# EIT_Teensy_Mux.net
KiCad netlist of a schematic drawn in Altium Designer
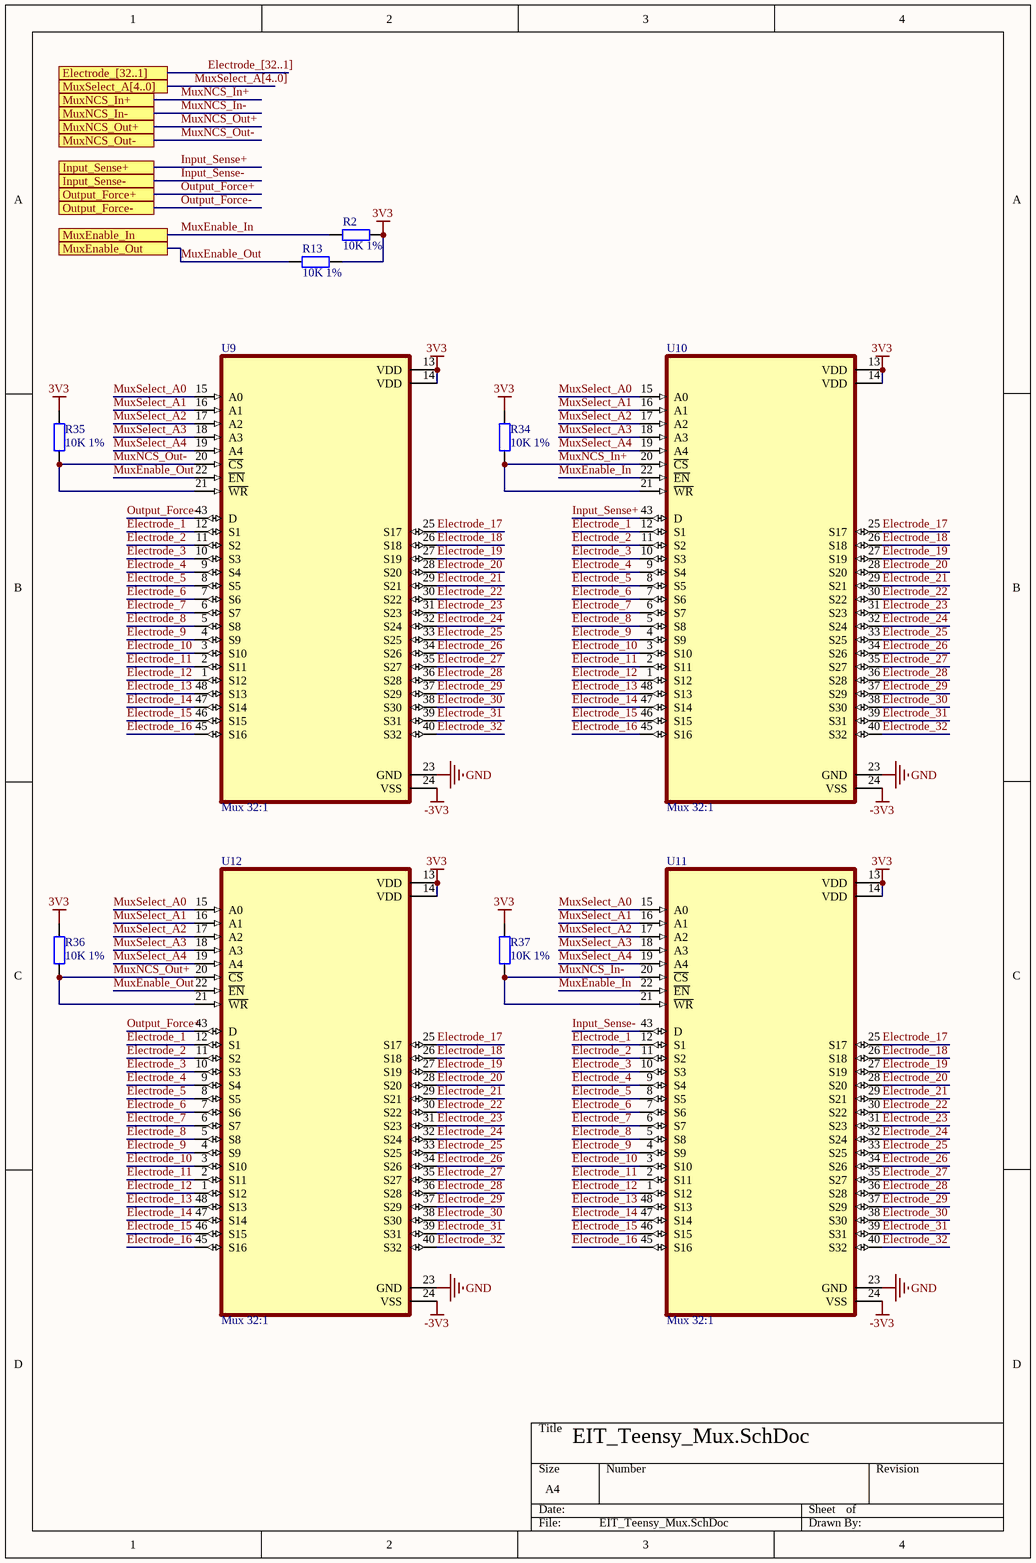
[diagram p0: EIT_Teensy_Mux.SchDoc]

(export (version "E")
  (design (tool "Eeschema 10.0.6"))
  (components
    (comp (ref "R2")
      (value "10K 1%")
      (footprint "0603 RES")
      (description "Res General Purpose Thick Film 0603 10K Ohm 1% 1/10W ±100ppm/°C Molded SMD Paper T/R")
      (fields
        (field (name "MANUFACTURER") "Yageo")
        (field (name "MANUFACTURER PART NUMBER") "RC0603FR-0710KL")
      )
      (libsource (lib "EitLib") (part "Res 0603 10K 1%"))
    )
    (comp (ref "R13")
      (value "10K 1%")
      (footprint "0603 RES")
      (description "Res General Purpose Thick Film 0603 10K Ohm 1% 1/10W ±100ppm/°C Molded SMD Paper T/R")
      (fields
        (field (name "MANUFACTURER") "Yageo")
        (field (name "MANUFACTURER PART NUMBER") "RC0603FR-0710KL")
      )
      (libsource (lib "EitLib") (part "Res 0603 10K 1%"))
    )
    (comp (ref "R34")
      (value "10K 1%")
      (footprint "0603 RES")
      (description "Res General Purpose Thick Film 0603 10K Ohm 1% 1/10W ±100ppm/°C Molded SMD Paper T/R")
      (fields
        (field (name "MANUFACTURER") "Yageo")
        (field (name "MANUFACTURER PART NUMBER") "RC0603FR-0710KL")
      )
      (libsource (lib "") (part "Res 0603 10K 1%_1"))
    )
    (comp (ref "R35")
      (value "10K 1%")
      (footprint "0603 RES")
      (description "Res General Purpose Thick Film 0603 10K Ohm 1% 1/10W ±100ppm/°C Molded SMD Paper T/R")
      (fields
        (field (name "MANUFACTURER") "Yageo")
        (field (name "MANUFACTURER PART NUMBER") "RC0603FR-0710KL")
      )
      (libsource (lib "") (part "Res 0603 10K 1%_1"))
    )
    (comp (ref "R36")
      (value "10K 1%")
      (footprint "0603 RES")
      (description "Res General Purpose Thick Film 0603 10K Ohm 1% 1/10W ±100ppm/°C Molded SMD Paper T/R")
      (fields
        (field (name "MANUFACTURER") "Yageo")
        (field (name "MANUFACTURER PART NUMBER") "RC0603FR-0710KL")
      )
      (libsource (lib "") (part "Res 0603 10K 1%_1"))
    )
    (comp (ref "R37")
      (value "10K 1%")
      (footprint "0603 RES")
      (description "Res General Purpose Thick Film 0603 10K Ohm 1% 1/10W ±100ppm/°C Molded SMD Paper T/R")
      (fields
        (field (name "MANUFACTURER") "Yageo")
        (field (name "MANUFACTURER PART NUMBER") "RC0603FR-0710KL")
      )
      (libsource (lib "") (part "Res 0603 10K 1%_1"))
    )
    (comp (ref "U9")
      (value "Mux 32:1")
      (footprint "SnapEDApcb:QFP50P900X900X120-49N")
      (description "Analog Multiplexer Single 32:1 48-Pin TQFP T/R")
      (fields
        (field (name "MANUFACTURER") "Analog Devices")
        (field (name "MANUFACTURER PART NUMBER") "ADG732BSUZ-REEL")
      )
      (libsource (lib "EitLib") (part "Mux ADG732BSUZ"))
    )
    (comp (ref "U10")
      (value "Mux 32:1")
      (footprint "SnapEDApcb:QFP50P900X900X120-49N")
      (description "Analog Multiplexer Single 32:1 48-Pin TQFP T/R")
      (fields
        (field (name "MANUFACTURER") "Analog Devices")
        (field (name "MANUFACTURER PART NUMBER") "ADG732BSUZ-REEL")
      )
      (libsource (lib "EitLib") (part "Mux ADG732BSUZ"))
    )
    (comp (ref "U11")
      (value "Mux 32:1")
      (footprint "SnapEDApcb:QFP50P900X900X120-49N")
      (description "Analog Multiplexer Single 32:1 48-Pin TQFP T/R")
      (fields
        (field (name "MANUFACTURER") "Analog Devices")
        (field (name "MANUFACTURER PART NUMBER") "ADG732BSUZ-REEL")
      )
      (libsource (lib "EitLib") (part "Mux ADG732BSUZ"))
    )
    (comp (ref "U12")
      (value "Mux 32:1")
      (footprint "SnapEDApcb:QFP50P900X900X120-49N")
      (description "Analog Multiplexer Single 32:1 48-Pin TQFP T/R")
      (fields
        (field (name "MANUFACTURER") "Analog Devices")
        (field (name "MANUFACTURER PART NUMBER") "ADG732BSUZ-REEL")
      )
      (libsource (lib "EitLib") (part "Mux ADG732BSUZ"))
    )
  )
  (nets
    (net (code "1") (name "-3V3") (class "Default")
      (node (ref "U10") (pin "24") (pinfunction "VSS_24") (pintype "power_in"))
      (node (ref "U11") (pin "24") (pinfunction "VSS_24") (pintype "power_in"))
      (node (ref "U12") (pin "24") (pinfunction "VSS_24") (pintype "power_in"))
      (node (ref "U9") (pin "24") (pinfunction "VSS_24") (pintype "power_in"))
    )
    (net (code "2") (name "/Electrode_1") (class "Default")
      (node (ref "U10") (pin "12") (pinfunction "S1_12") (pintype "bidirectional"))
      (node (ref "U11") (pin "12") (pinfunction "S1_12") (pintype "bidirectional"))
      (node (ref "U12") (pin "12") (pinfunction "S1_12") (pintype "bidirectional"))
      (node (ref "U9") (pin "12") (pinfunction "S1_12") (pintype "bidirectional"))
    )
    (net (code "3") (name "/Electrode_2") (class "Default")
      (node (ref "U10") (pin "11") (pinfunction "S2_11") (pintype "bidirectional"))
      (node (ref "U11") (pin "11") (pinfunction "S2_11") (pintype "bidirectional"))
      (node (ref "U12") (pin "11") (pinfunction "S2_11") (pintype "bidirectional"))
      (node (ref "U9") (pin "11") (pinfunction "S2_11") (pintype "bidirectional"))
    )
    (net (code "4") (name "/Electrode_3") (class "Default")
      (node (ref "U10") (pin "10") (pinfunction "S3_10") (pintype "bidirectional"))
      (node (ref "U11") (pin "10") (pinfunction "S3_10") (pintype "bidirectional"))
      (node (ref "U12") (pin "10") (pinfunction "S3_10") (pintype "bidirectional"))
      (node (ref "U9") (pin "10") (pinfunction "S3_10") (pintype "bidirectional"))
    )
    (net (code "5") (name "/Electrode_4") (class "Default")
      (node (ref "U10") (pin "9") (pinfunction "S4_9") (pintype "bidirectional"))
      (node (ref "U11") (pin "9") (pinfunction "S4_9") (pintype "bidirectional"))
      (node (ref "U12") (pin "9") (pinfunction "S4_9") (pintype "bidirectional"))
      (node (ref "U9") (pin "9") (pinfunction "S4_9") (pintype "bidirectional"))
    )
    (net (code "6") (name "/Electrode_5") (class "Default")
      (node (ref "U10") (pin "8") (pinfunction "S5_8") (pintype "bidirectional"))
      (node (ref "U11") (pin "8") (pinfunction "S5_8") (pintype "bidirectional"))
      (node (ref "U12") (pin "8") (pinfunction "S5_8") (pintype "bidirectional"))
      (node (ref "U9") (pin "8") (pinfunction "S5_8") (pintype "bidirectional"))
    )
    (net (code "7") (name "/Electrode_6") (class "Default")
      (node (ref "U10") (pin "7") (pinfunction "S6_7") (pintype "bidirectional"))
      (node (ref "U11") (pin "7") (pinfunction "S6_7") (pintype "bidirectional"))
      (node (ref "U12") (pin "7") (pinfunction "S6_7") (pintype "bidirectional"))
      (node (ref "U9") (pin "7") (pinfunction "S6_7") (pintype "bidirectional"))
    )
    (net (code "8") (name "/Electrode_7") (class "Default")
      (node (ref "U10") (pin "6") (pinfunction "S7_6") (pintype "bidirectional"))
      (node (ref "U11") (pin "6") (pinfunction "S7_6") (pintype "bidirectional"))
      (node (ref "U12") (pin "6") (pinfunction "S7_6") (pintype "bidirectional"))
      (node (ref "U9") (pin "6") (pinfunction "S7_6") (pintype "bidirectional"))
    )
    (net (code "9") (name "/Electrode_8") (class "Default")
      (node (ref "U10") (pin "5") (pinfunction "S8_5") (pintype "bidirectional"))
      (node (ref "U11") (pin "5") (pinfunction "S8_5") (pintype "bidirectional"))
      (node (ref "U12") (pin "5") (pinfunction "S8_5") (pintype "bidirectional"))
      (node (ref "U9") (pin "5") (pinfunction "S8_5") (pintype "bidirectional"))
    )
    (net (code "10") (name "/Electrode_9") (class "Default")
      (node (ref "U10") (pin "4") (pinfunction "S9_4") (pintype "bidirectional"))
      (node (ref "U11") (pin "4") (pinfunction "S9_4") (pintype "bidirectional"))
      (node (ref "U12") (pin "4") (pinfunction "S9_4") (pintype "bidirectional"))
      (node (ref "U9") (pin "4") (pinfunction "S9_4") (pintype "bidirectional"))
    )
    (net (code "11") (name "/Electrode_10") (class "Default")
      (node (ref "U10") (pin "3") (pinfunction "S10_3") (pintype "bidirectional"))
      (node (ref "U11") (pin "3") (pinfunction "S10_3") (pintype "bidirectional"))
      (node (ref "U12") (pin "3") (pinfunction "S10_3") (pintype "bidirectional"))
      (node (ref "U9") (pin "3") (pinfunction "S10_3") (pintype "bidirectional"))
    )
    (net (code "12") (name "/Electrode_11") (class "Default")
      (node (ref "U10") (pin "2") (pinfunction "S11_2") (pintype "bidirectional"))
      (node (ref "U11") (pin "2") (pinfunction "S11_2") (pintype "bidirectional"))
      (node (ref "U12") (pin "2") (pinfunction "S11_2") (pintype "bidirectional"))
      (node (ref "U9") (pin "2") (pinfunction "S11_2") (pintype "bidirectional"))
    )
    (net (code "13") (name "/Electrode_12") (class "Default")
      (node (ref "U10") (pin "1") (pinfunction "S12_1") (pintype "bidirectional"))
      (node (ref "U11") (pin "1") (pinfunction "S12_1") (pintype "bidirectional"))
      (node (ref "U12") (pin "1") (pinfunction "S12_1") (pintype "bidirectional"))
      (node (ref "U9") (pin "1") (pinfunction "S12_1") (pintype "bidirectional"))
    )
    (net (code "14") (name "/Electrode_13") (class "Default")
      (node (ref "U10") (pin "48") (pinfunction "S13_48") (pintype "bidirectional"))
      (node (ref "U11") (pin "48") (pinfunction "S13_48") (pintype "bidirectional"))
      (node (ref "U12") (pin "48") (pinfunction "S13_48") (pintype "bidirectional"))
      (node (ref "U9") (pin "48") (pinfunction "S13_48") (pintype "bidirectional"))
    )
    (net (code "15") (name "/Electrode_14") (class "Default")
      (node (ref "U10") (pin "47") (pinfunction "S14_47") (pintype "bidirectional"))
      (node (ref "U11") (pin "47") (pinfunction "S14_47") (pintype "bidirectional"))
      (node (ref "U12") (pin "47") (pinfunction "S14_47") (pintype "bidirectional"))
      (node (ref "U9") (pin "47") (pinfunction "S14_47") (pintype "bidirectional"))
    )
    (net (code "16") (name "/Electrode_15") (class "Default")
      (node (ref "U10") (pin "46") (pinfunction "S15_46") (pintype "bidirectional"))
      (node (ref "U11") (pin "46") (pinfunction "S15_46") (pintype "bidirectional"))
      (node (ref "U12") (pin "46") (pinfunction "S15_46") (pintype "bidirectional"))
      (node (ref "U9") (pin "46") (pinfunction "S15_46") (pintype "bidirectional"))
    )
    (net (code "17") (name "/Electrode_16") (class "Default")
      (node (ref "U10") (pin "45") (pinfunction "S16_45") (pintype "bidirectional"))
      (node (ref "U11") (pin "45") (pinfunction "S16_45") (pintype "bidirectional"))
      (node (ref "U12") (pin "45") (pinfunction "S16_45") (pintype "bidirectional"))
      (node (ref "U9") (pin "45") (pinfunction "S16_45") (pintype "bidirectional"))
    )
    (net (code "18") (name "/Electrode_17") (class "Default")
      (node (ref "U10") (pin "25") (pinfunction "S17_25") (pintype "bidirectional"))
      (node (ref "U11") (pin "25") (pinfunction "S17_25") (pintype "bidirectional"))
      (node (ref "U12") (pin "25") (pinfunction "S17_25") (pintype "bidirectional"))
      (node (ref "U9") (pin "25") (pinfunction "S17_25") (pintype "bidirectional"))
    )
    (net (code "19") (name "/Electrode_18") (class "Default")
      (node (ref "U10") (pin "26") (pinfunction "S18_26") (pintype "bidirectional"))
      (node (ref "U11") (pin "26") (pinfunction "S18_26") (pintype "bidirectional"))
      (node (ref "U12") (pin "26") (pinfunction "S18_26") (pintype "bidirectional"))
      (node (ref "U9") (pin "26") (pinfunction "S18_26") (pintype "bidirectional"))
    )
    (net (code "20") (name "/Electrode_19") (class "Default")
      (node (ref "U10") (pin "27") (pinfunction "S19_27") (pintype "bidirectional"))
      (node (ref "U11") (pin "27") (pinfunction "S19_27") (pintype "bidirectional"))
      (node (ref "U12") (pin "27") (pinfunction "S19_27") (pintype "bidirectional"))
      (node (ref "U9") (pin "27") (pinfunction "S19_27") (pintype "bidirectional"))
    )
    (net (code "21") (name "/Electrode_20") (class "Default")
      (node (ref "U10") (pin "28") (pinfunction "S20_28") (pintype "bidirectional"))
      (node (ref "U11") (pin "28") (pinfunction "S20_28") (pintype "bidirectional"))
      (node (ref "U12") (pin "28") (pinfunction "S20_28") (pintype "bidirectional"))
      (node (ref "U9") (pin "28") (pinfunction "S20_28") (pintype "bidirectional"))
    )
    (net (code "22") (name "/Electrode_21") (class "Default")
      (node (ref "U10") (pin "29") (pinfunction "S21_29") (pintype "bidirectional"))
      (node (ref "U11") (pin "29") (pinfunction "S21_29") (pintype "bidirectional"))
      (node (ref "U12") (pin "29") (pinfunction "S21_29") (pintype "bidirectional"))
      (node (ref "U9") (pin "29") (pinfunction "S21_29") (pintype "bidirectional"))
    )
    (net (code "23") (name "/Electrode_22") (class "Default")
      (node (ref "U10") (pin "30") (pinfunction "S22_30") (pintype "bidirectional"))
      (node (ref "U11") (pin "30") (pinfunction "S22_30") (pintype "bidirectional"))
      (node (ref "U12") (pin "30") (pinfunction "S22_30") (pintype "bidirectional"))
      (node (ref "U9") (pin "30") (pinfunction "S22_30") (pintype "bidirectional"))
    )
    (net (code "24") (name "/Electrode_23") (class "Default")
      (node (ref "U10") (pin "31") (pinfunction "S23_31") (pintype "bidirectional"))
      (node (ref "U11") (pin "31") (pinfunction "S23_31") (pintype "bidirectional"))
      (node (ref "U12") (pin "31") (pinfunction "S23_31") (pintype "bidirectional"))
      (node (ref "U9") (pin "31") (pinfunction "S23_31") (pintype "bidirectional"))
    )
    (net (code "25") (name "/Electrode_24") (class "Default")
      (node (ref "U10") (pin "32") (pinfunction "S24_32") (pintype "bidirectional"))
      (node (ref "U11") (pin "32") (pinfunction "S24_32") (pintype "bidirectional"))
      (node (ref "U12") (pin "32") (pinfunction "S24_32") (pintype "bidirectional"))
      (node (ref "U9") (pin "32") (pinfunction "S24_32") (pintype "bidirectional"))
    )
    (net (code "26") (name "/Electrode_25") (class "Default")
      (node (ref "U10") (pin "33") (pinfunction "S25_33") (pintype "bidirectional"))
      (node (ref "U11") (pin "33") (pinfunction "S25_33") (pintype "bidirectional"))
      (node (ref "U12") (pin "33") (pinfunction "S25_33") (pintype "bidirectional"))
      (node (ref "U9") (pin "33") (pinfunction "S25_33") (pintype "bidirectional"))
    )
    (net (code "27") (name "/Electrode_26") (class "Default")
      (node (ref "U10") (pin "34") (pinfunction "S26_34") (pintype "bidirectional"))
      (node (ref "U11") (pin "34") (pinfunction "S26_34") (pintype "bidirectional"))
      (node (ref "U12") (pin "34") (pinfunction "S26_34") (pintype "bidirectional"))
      (node (ref "U9") (pin "34") (pinfunction "S26_34") (pintype "bidirectional"))
    )
    (net (code "28") (name "/Electrode_27") (class "Default")
      (node (ref "U10") (pin "35") (pinfunction "S27_35") (pintype "bidirectional"))
      (node (ref "U11") (pin "35") (pinfunction "S27_35") (pintype "bidirectional"))
      (node (ref "U12") (pin "35") (pinfunction "S27_35") (pintype "bidirectional"))
      (node (ref "U9") (pin "35") (pinfunction "S27_35") (pintype "bidirectional"))
    )
    (net (code "29") (name "/Electrode_28") (class "Default")
      (node (ref "U10") (pin "36") (pinfunction "S28_36") (pintype "bidirectional"))
      (node (ref "U11") (pin "36") (pinfunction "S28_36") (pintype "bidirectional"))
      (node (ref "U12") (pin "36") (pinfunction "S28_36") (pintype "bidirectional"))
      (node (ref "U9") (pin "36") (pinfunction "S28_36") (pintype "bidirectional"))
    )
    (net (code "30") (name "/Electrode_29") (class "Default")
      (node (ref "U10") (pin "37") (pinfunction "S29_37") (pintype "bidirectional"))
      (node (ref "U11") (pin "37") (pinfunction "S29_37") (pintype "bidirectional"))
      (node (ref "U12") (pin "37") (pinfunction "S29_37") (pintype "bidirectional"))
      (node (ref "U9") (pin "37") (pinfunction "S29_37") (pintype "bidirectional"))
    )
    (net (code "31") (name "/Electrode_30") (class "Default")
      (node (ref "U10") (pin "38") (pinfunction "S30_38") (pintype "bidirectional"))
      (node (ref "U11") (pin "38") (pinfunction "S30_38") (pintype "bidirectional"))
      (node (ref "U12") (pin "38") (pinfunction "S30_38") (pintype "bidirectional"))
      (node (ref "U9") (pin "38") (pinfunction "S30_38") (pintype "bidirectional"))
    )
    (net (code "32") (name "/Electrode_31") (class "Default")
      (node (ref "U10") (pin "39") (pinfunction "S31_39") (pintype "bidirectional"))
      (node (ref "U11") (pin "39") (pinfunction "S31_39") (pintype "bidirectional"))
      (node (ref "U12") (pin "39") (pinfunction "S31_39") (pintype "bidirectional"))
      (node (ref "U9") (pin "39") (pinfunction "S31_39") (pintype "bidirectional"))
    )
    (net (code "33") (name "/Electrode_32") (class "Default")
      (node (ref "U10") (pin "40") (pinfunction "S32_40") (pintype "bidirectional"))
      (node (ref "U11") (pin "40") (pinfunction "S32_40") (pintype "bidirectional"))
      (node (ref "U12") (pin "40") (pinfunction "S32_40") (pintype "bidirectional"))
      (node (ref "U9") (pin "40") (pinfunction "S32_40") (pintype "bidirectional"))
    )
    (net (code "35") (name "/Input_Sense+") (class "Default")
      (node (ref "U10") (pin "43") (pinfunction "D_43") (pintype "bidirectional"))
    )
    (net (code "36") (name "/Input_Sense-") (class "Default")
      (node (ref "U11") (pin "43") (pinfunction "D_43") (pintype "bidirectional"))
    )
    (net (code "37") (name "/MuxEnable_In") (class "Default")
      (node (ref "R2") (pin "1") (pinfunction "1_1") (pintype "passive"))
      (node (ref "U10") (pin "22") (pinfunction "~{EN}_22") (pintype "input"))
      (node (ref "U11") (pin "22") (pinfunction "~{EN}_22") (pintype "input"))
    )
    (net (code "38") (name "/MuxEnable_Out") (class "Default")
      (node (ref "R13") (pin "1") (pinfunction "1_1") (pintype "passive"))
      (node (ref "U12") (pin "22") (pinfunction "~{EN}_22") (pintype "input"))
      (node (ref "U9") (pin "22") (pinfunction "~{EN}_22") (pintype "input"))
    )
    (net (code "39") (name "/MuxNCS_In+") (class "Default")
      (node (ref "R34") (pin "1") (pinfunction "1_1") (pintype "passive"))
      (node (ref "U10") (pin "20") (pinfunction "~{CS}_20") (pintype "input"))
      (node (ref "U10") (pin "21") (pinfunction "~{WR}_21") (pintype "input"))
    )
    (net (code "40") (name "/MuxNCS_In-") (class "Default")
      (node (ref "R37") (pin "1") (pinfunction "1_1") (pintype "passive"))
      (node (ref "U11") (pin "20") (pinfunction "~{CS}_20") (pintype "input"))
      (node (ref "U11") (pin "21") (pinfunction "~{WR}_21") (pintype "input"))
    )
    (net (code "41") (name "/MuxNCS_Out+") (class "Default")
      (node (ref "R36") (pin "1") (pinfunction "1_1") (pintype "passive"))
      (node (ref "U12") (pin "20") (pinfunction "~{CS}_20") (pintype "input"))
      (node (ref "U12") (pin "21") (pinfunction "~{WR}_21") (pintype "input"))
    )
    (net (code "42") (name "/MuxNCS_Out-") (class "Default")
      (node (ref "R35") (pin "1") (pinfunction "1_1") (pintype "passive"))
      (node (ref "U9") (pin "20") (pinfunction "~{CS}_20") (pintype "input"))
      (node (ref "U9") (pin "21") (pinfunction "~{WR}_21") (pintype "input"))
    )
    (net (code "43") (name "/MuxSelect_A0") (class "Default")
      (node (ref "U10") (pin "15") (pinfunction "A0_15") (pintype "input"))
      (node (ref "U11") (pin "15") (pinfunction "A0_15") (pintype "input"))
      (node (ref "U12") (pin "15") (pinfunction "A0_15") (pintype "input"))
      (node (ref "U9") (pin "15") (pinfunction "A0_15") (pintype "input"))
    )
    (net (code "44") (name "/MuxSelect_A1") (class "Default")
      (node (ref "U10") (pin "16") (pinfunction "A1_16") (pintype "input"))
      (node (ref "U11") (pin "16") (pinfunction "A1_16") (pintype "input"))
      (node (ref "U12") (pin "16") (pinfunction "A1_16") (pintype "input"))
      (node (ref "U9") (pin "16") (pinfunction "A1_16") (pintype "input"))
    )
    (net (code "45") (name "/MuxSelect_A2") (class "Default")
      (node (ref "U10") (pin "17") (pinfunction "A2_17") (pintype "input"))
      (node (ref "U11") (pin "17") (pinfunction "A2_17") (pintype "input"))
      (node (ref "U12") (pin "17") (pinfunction "A2_17") (pintype "input"))
      (node (ref "U9") (pin "17") (pinfunction "A2_17") (pintype "input"))
    )
    (net (code "46") (name "/MuxSelect_A3") (class "Default")
      (node (ref "U10") (pin "18") (pinfunction "A3_18") (pintype "input"))
      (node (ref "U11") (pin "18") (pinfunction "A3_18") (pintype "input"))
      (node (ref "U12") (pin "18") (pinfunction "A3_18") (pintype "input"))
      (node (ref "U9") (pin "18") (pinfunction "A3_18") (pintype "input"))
    )
    (net (code "47") (name "/MuxSelect_A4") (class "Default")
      (node (ref "U10") (pin "19") (pinfunction "A4_19") (pintype "input"))
      (node (ref "U11") (pin "19") (pinfunction "A4_19") (pintype "input"))
      (node (ref "U12") (pin "19") (pinfunction "A4_19") (pintype "input"))
      (node (ref "U9") (pin "19") (pinfunction "A4_19") (pintype "input"))
    )
    (net (code "49") (name "/Output_Force+") (class "Default")
      (node (ref "U12") (pin "43") (pinfunction "D_43") (pintype "bidirectional"))
    )
    (net (code "50") (name "/Output_Force-") (class "Default")
      (node (ref "U9") (pin "43") (pinfunction "D_43") (pintype "bidirectional"))
    )
    (net (code "51") (name "3V3") (class "Default")
      (node (ref "R13") (pin "2") (pinfunction "2_2") (pintype "passive"))
      (node (ref "R2") (pin "2") (pinfunction "2_2") (pintype "passive"))
      (node (ref "R34") (pin "2") (pinfunction "2_2") (pintype "passive"))
      (node (ref "R35") (pin "2") (pinfunction "2_2") (pintype "passive"))
      (node (ref "R36") (pin "2") (pinfunction "2_2") (pintype "passive"))
      (node (ref "R37") (pin "2") (pinfunction "2_2") (pintype "passive"))
      (node (ref "U10") (pin "13") (pinfunction "VDD_13") (pintype "power_in"))
      (node (ref "U10") (pin "14") (pinfunction "VDD_14") (pintype "power_in"))
      (node (ref "U11") (pin "13") (pinfunction "VDD_13") (pintype "power_in"))
      (node (ref "U11") (pin "14") (pinfunction "VDD_14") (pintype "power_in"))
      (node (ref "U12") (pin "13") (pinfunction "VDD_13") (pintype "power_in"))
      (node (ref "U12") (pin "14") (pinfunction "VDD_14") (pintype "power_in"))
      (node (ref "U9") (pin "13") (pinfunction "VDD_13") (pintype "power_in"))
      (node (ref "U9") (pin "14") (pinfunction "VDD_14") (pintype "power_in"))
    )
    (net (code "52") (name "GND") (class "Default")
      (node (ref "U10") (pin "23") (pinfunction "GND_23") (pintype "power_in"))
      (node (ref "U11") (pin "23") (pinfunction "GND_23") (pintype "power_in"))
      (node (ref "U12") (pin "23") (pinfunction "GND_23") (pintype "power_in"))
      (node (ref "U9") (pin "23") (pinfunction "GND_23") (pintype "power_in"))
    )
  )
)
